# Usb_SdCard.net
KiCad netlist of a schematic drawn in Altium Designer
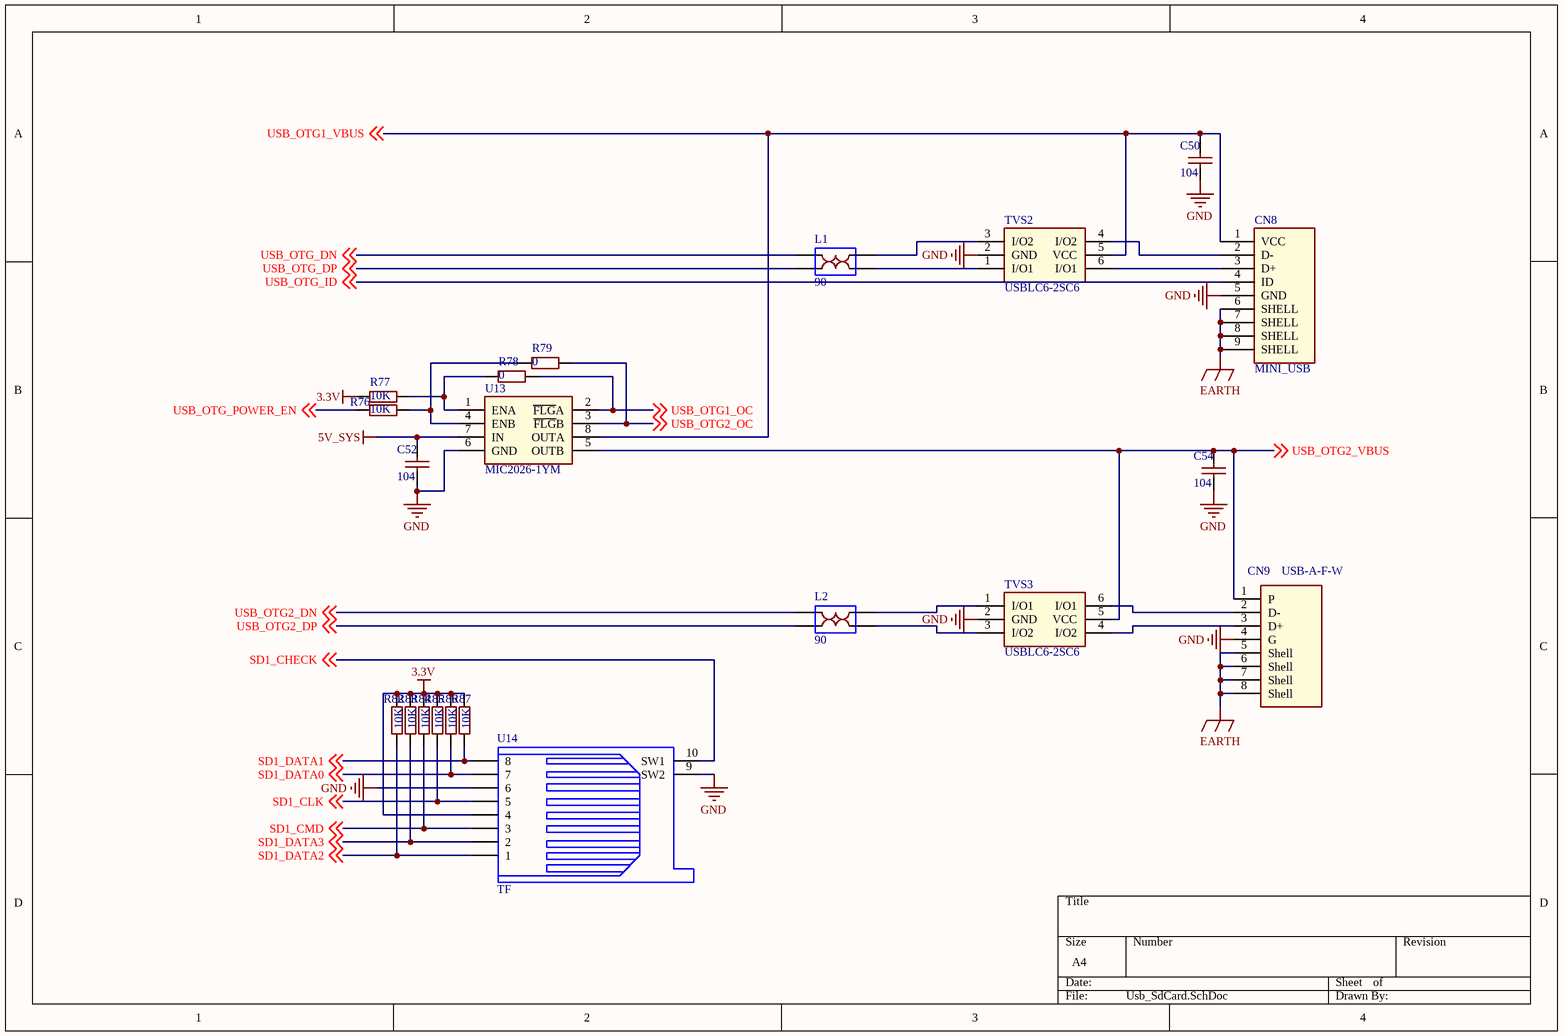
[diagram p0: Usb_SdCard.SchDoc]

(export (version "E")
  (design (tool "Eeschema 10.0.6"))
  (components
    (comp (ref "C50")
      (value "104")
      (footprint "0805SMD_Cap")
      (description "贴片电容")
      (libsource (lib "ST_GND_Sch") (part "SMD_Cap"))
    )
    (comp (ref "C52")
      (value "104")
      (footprint "0805SMD_Cap")
      (description "贴片电容")
      (libsource (lib "ST_GND_Sch") (part "SMD_Cap"))
    )
    (comp (ref "C54")
      (value "104")
      (footprint "0805SMD_Cap")
      (description "贴片电容")
      (libsource (lib "ST_GND_Sch") (part "SMD_Cap"))
    )
    (comp (ref "CN8")
      (value "MINI_USB")
      (footprint "MICRO_USB")
      (libsource (lib "ST_GND_Sch") (part "MINI_USB"))
    )
    (comp (ref "CN9")
      (value "USB-A-F-W")
      (footprint "USB-C")
      (libsource (lib "ST_GND_Sch") (part "USB-A-F-W"))
    )
    (comp (ref "L1") (value "90") (footprint "2012") (libsource (lib "ST_GND_Sch") (part "共模电感")))
    (comp (ref "L2") (value "90") (footprint "2012") (libsource (lib "") (part "共模电感_1")))
    (comp (ref "R76")
      (value "10K")
      (footprint "0805_SMD_R")
      (description "贴片电阻")
      (libsource (lib "ST_GND_Sch") (part "SMD_0805"))
    )
    (comp (ref "R77")
      (value "10K")
      (footprint "0805_SMD_R")
      (description "贴片电阻")
      (libsource (lib "ST_GND_Sch") (part "SMD_0805"))
    )
    (comp (ref "R78")
      (value "0")
      (footprint "0805_SMD_R")
      (description "贴片电阻")
      (libsource (lib "ST_GND_Sch") (part "SMD_0805"))
    )
    (comp (ref "R79")
      (value "0")
      (footprint "0805_SMD_R")
      (description "贴片电阻")
      (libsource (lib "ST_GND_Sch") (part "SMD_0805"))
    )
    (comp (ref "R82")
      (value "10K")
      (footprint "0805_SMD_R")
      (description "贴片电阻")
      (libsource (lib "") (part "SMD_0805_1"))
    )
    (comp (ref "R83")
      (value "10K")
      (footprint "0805_SMD_R")
      (description "贴片电阻")
      (libsource (lib "") (part "SMD_0805_1"))
    )
    (comp (ref "R84")
      (value "10K")
      (footprint "0805_SMD_R")
      (description "贴片电阻")
      (libsource (lib "") (part "SMD_0805_1"))
    )
    (comp (ref "R85")
      (value "10K")
      (footprint "0805_SMD_R")
      (description "贴片电阻")
      (libsource (lib "") (part "SMD_0805_1"))
    )
    (comp (ref "R86")
      (value "10K")
      (footprint "0805_SMD_R")
      (description "贴片电阻")
      (libsource (lib "") (part "SMD_0805_1"))
    )
    (comp (ref "R87")
      (value "10K")
      (footprint "0805_SMD_R")
      (description "贴片电阻")
      (libsource (lib "") (part "SMD_0805_1"))
    )
    (comp (ref "TVS2")
      (value "USBLC6-2SC6")
      (footprint "SOT-23-6")
      (libsource (lib "ST_GND_Sch") (part "USBLC6-2SC6"))
    )
    (comp (ref "TVS3")
      (value "USBLC6-2SC6")
      (footprint "SOT-23-6")
      (libsource (lib "") (part "USBLC6-2SC6_1"))
    )
    (comp (ref "U13")
      (value "MIC2026-1YM")
      (footprint "运放SO8")
      (libsource (lib "ST_GND_Sch") (part "MIC2026-1YM"))
    )
    (comp (ref "U14") (value "TF") (footprint "TF") (libsource (lib "ST_GND_Sch") (part "TF")))
  )
  (nets
    (net (code "1") (name "3.3V") (class "Default")
      (node (ref "R77") (pin "2") (pinfunction "2_2") (pintype "passive"))
      (node (ref "R82") (pin "2") (pinfunction "2_2") (pintype "passive"))
      (node (ref "R83") (pin "2") (pinfunction "2_2") (pintype "passive"))
      (node (ref "R84") (pin "2") (pinfunction "2_2") (pintype "passive"))
      (node (ref "R85") (pin "2") (pinfunction "2_2") (pintype "passive"))
      (node (ref "R86") (pin "2") (pinfunction "2_2") (pintype "passive"))
      (node (ref "R87") (pin "2") (pinfunction "2_2") (pintype "passive"))
      (node (ref "U14") (pin "4") (pinfunction "4_4") (pintype "passive"))
    )
    (net (code "2") (name "5V_SYS") (class "Default")
      (node (ref "C52") (pin "1") (pintype "passive"))
      (node (ref "U13") (pin "7") (pinfunction "IN_7") (pintype "passive"))
    )
    (net (code "3") (name "EARTH") (class "Default")
      (node (ref "CN8") (pin "6") (pinfunction "SHELL_6") (pintype "passive"))
      (node (ref "CN8") (pin "7") (pinfunction "SHELL_7") (pintype "passive"))
      (node (ref "CN8") (pin "8") (pinfunction "SHELL_8") (pintype "passive"))
      (node (ref "CN8") (pin "9") (pinfunction "SHELL_9") (pintype "passive"))
      (node (ref "CN9") (pin "5") (pinfunction "Shell_5") (pintype "passive"))
      (node (ref "CN9") (pin "6") (pinfunction "Shell_6") (pintype "passive"))
      (node (ref "CN9") (pin "7") (pinfunction "Shell_7") (pintype "power_in"))
      (node (ref "CN9") (pin "8") (pinfunction "Shell_8") (pintype "power_in"))
    )
    (net (code "4") (name "GND") (class "Default")
      (node (ref "C50") (pin "2") (pintype "passive"))
      (node (ref "C52") (pin "2") (pintype "passive"))
      (node (ref "C54") (pin "2") (pintype "passive"))
      (node (ref "CN8") (pin "5") (pinfunction "GND_5") (pintype "power_in"))
      (node (ref "CN9") (pin "4") (pinfunction "G_4") (pintype "passive"))
      (node (ref "TVS2") (pin "2") (pinfunction "GND_2") (pintype "passive"))
      (node (ref "TVS3") (pin "2") (pinfunction "GND_2") (pintype "passive"))
      (node (ref "U13") (pin "6") (pinfunction "GND_6") (pintype "passive"))
      (node (ref "U14") (pin "6") (pinfunction "6_6") (pintype "passive"))
      (node (ref "U14") (pin "9") (pinfunction "SW2_9") (pintype "passive"))
    )
    (net (code "5") (name "Net-(CN8-D+)") (class "Default")
      (node (ref "CN8") (pin "3") (pinfunction "D+_3") (pintype "passive"))
      (node (ref "TVS2") (pin "6") (pinfunction "I/O1_6") (pintype "passive"))
    )
    (net (code "6") (name "Net-(CN8-D-)") (class "Default")
      (node (ref "CN8") (pin "2") (pinfunction "D-_2") (pintype "passive"))
      (node (ref "TVS2") (pin "4") (pinfunction "I/O2_4") (pintype "passive"))
    )
    (net (code "7") (name "Net-(CN9-D+)") (class "Default")
      (node (ref "CN9") (pin "3") (pinfunction "D+_3") (pintype "passive"))
      (node (ref "TVS3") (pin "4") (pinfunction "I/O2_4") (pintype "passive"))
    )
    (net (code "8") (name "Net-(CN9-D-)") (class "Default")
      (node (ref "CN9") (pin "2") (pinfunction "D-_2") (pintype "passive"))
      (node (ref "TVS3") (pin "6") (pinfunction "I/O1_6") (pintype "passive"))
    )
    (net (code "9") (name "Net-(L1-Pad3)") (class "Default")
      (node (ref "L1") (pin "3") (pinfunction "3_3") (pintype "passive"))
      (node (ref "TVS2") (pin "3") (pinfunction "I/O2_3") (pintype "passive"))
    )
    (net (code "10") (name "Net-(L1-Pad4)") (class "Default")
      (node (ref "L1") (pin "4") (pinfunction "4_4") (pintype "passive"))
      (node (ref "TVS2") (pin "1") (pinfunction "I/O1_1") (pintype "passive"))
    )
    (net (code "11") (name "Net-(L2-Pad3)") (class "Default")
      (node (ref "L2") (pin "3") (pinfunction "3_3") (pintype "passive"))
      (node (ref "TVS3") (pin "3") (pinfunction "I/O2_3") (pintype "passive"))
    )
    (net (code "12") (name "Net-(L2-Pad4)") (class "Default")
      (node (ref "L2") (pin "4") (pinfunction "4_4") (pintype "passive"))
      (node (ref "TVS3") (pin "1") (pinfunction "I/O1_1") (pintype "passive"))
    )
    (net (code "13") (name "Net-(U13-ENA)") (class "Default")
      (node (ref "R77") (pin "1") (pinfunction "1_1") (pintype "passive"))
      (node (ref "R78") (pin "2") (pinfunction "2_2") (pintype "passive"))
      (node (ref "U13") (pin "1") (pinfunction "ENA_1") (pintype "passive"))
    )
    (net (code "14") (name "Net-(U13-ENB)") (class "Default")
      (node (ref "R76") (pin "1") (pinfunction "1_1") (pintype "passive"))
      (node (ref "R79") (pin "2") (pinfunction "2_2") (pintype "passive"))
      (node (ref "U13") (pin "4") (pinfunction "ENB_4") (pintype "passive"))
    )
    (net (code "15") (name "SD1_CHECK") (class "Default")
      (node (ref "U14") (pin "10") (pinfunction "SW1_10") (pintype "passive"))
    )
    (net (code "16") (name "SD1_CLK") (class "Default")
      (node (ref "R85") (pin "1") (pinfunction "1_1") (pintype "passive"))
      (node (ref "U14") (pin "5") (pinfunction "5_5") (pintype "passive"))
    )
    (net (code "17") (name "SD1_CMD") (class "Default")
      (node (ref "R84") (pin "1") (pinfunction "1_1") (pintype "passive"))
      (node (ref "U14") (pin "3") (pinfunction "3_3") (pintype "passive"))
    )
    (net (code "18") (name "SD1_DATA0") (class "Default")
      (node (ref "R86") (pin "1") (pinfunction "1_1") (pintype "passive"))
      (node (ref "U14") (pin "7") (pinfunction "7_7") (pintype "passive"))
    )
    (net (code "19") (name "SD1_DATA1") (class "Default")
      (node (ref "R87") (pin "1") (pinfunction "1_1") (pintype "passive"))
      (node (ref "U14") (pin "8") (pinfunction "8_8") (pintype "passive"))
    )
    (net (code "20") (name "SD1_DATA2") (class "Default")
      (node (ref "R82") (pin "1") (pinfunction "1_1") (pintype "passive"))
      (node (ref "U14") (pin "1") (pinfunction "1_1") (pintype "passive"))
    )
    (net (code "21") (name "SD1_DATA3") (class "Default")
      (node (ref "R83") (pin "1") (pinfunction "1_1") (pintype "passive"))
      (node (ref "U14") (pin "2") (pinfunction "2_2") (pintype "passive"))
    )
    (net (code "22") (name "USB_OTG1_OC") (class "Default")
      (node (ref "R78") (pin "1") (pinfunction "1_1") (pintype "passive"))
      (node (ref "U13") (pin "2") (pinfunction "~{FLG}A_2") (pintype "passive"))
    )
    (net (code "23") (name "USB_OTG1_VBUS") (class "Default")
      (node (ref "C50") (pin "1") (pintype "passive"))
      (node (ref "CN8") (pin "1") (pinfunction "VCC_1") (pintype "power_in"))
      (node (ref "TVS2") (pin "5") (pinfunction "VCC_5") (pintype "passive"))
      (node (ref "U13") (pin "8") (pinfunction "OUTA_8") (pintype "passive"))
    )
    (net (code "24") (name "USB_OTG2_DN") (class "Default")
      (node (ref "L2") (pin "1") (pinfunction "1_1") (pintype "passive"))
    )
    (net (code "25") (name "USB_OTG2_DP") (class "Default")
      (node (ref "L2") (pin "2") (pinfunction "2_2") (pintype "passive"))
    )
    (net (code "26") (name "USB_OTG2_OC") (class "Default")
      (node (ref "R79") (pin "1") (pinfunction "1_1") (pintype "passive"))
      (node (ref "U13") (pin "3") (pinfunction "~{FLG}B_3") (pintype "passive"))
    )
    (net (code "27") (name "USB_OTG2_VBUS") (class "Default")
      (node (ref "C54") (pin "1") (pintype "passive"))
      (node (ref "CN9") (pin "1") (pinfunction "P_1") (pintype "passive"))
      (node (ref "TVS3") (pin "5") (pinfunction "VCC_5") (pintype "passive"))
      (node (ref "U13") (pin "5") (pinfunction "OUTB_5") (pintype "passive"))
    )
    (net (code "28") (name "USB_OTG_DN") (class "Default")
      (node (ref "L1") (pin "2") (pinfunction "2_2") (pintype "passive"))
    )
    (net (code "29") (name "USB_OTG_DP") (class "Default")
      (node (ref "L1") (pin "1") (pinfunction "1_1") (pintype "passive"))
    )
    (net (code "30") (name "USB_OTG_ID") (class "Default")
      (node (ref "CN8") (pin "4") (pinfunction "ID_4") (pintype "passive"))
    )
    (net (code "31") (name "USB_OTG_POWER_EN") (class "Default")
      (node (ref "R76") (pin "2") (pinfunction "2_2") (pintype "passive"))
    )
  )
)
